# Atmega328P_Shield.net
KiCad netlist of a schematic drawn in Altium Designer
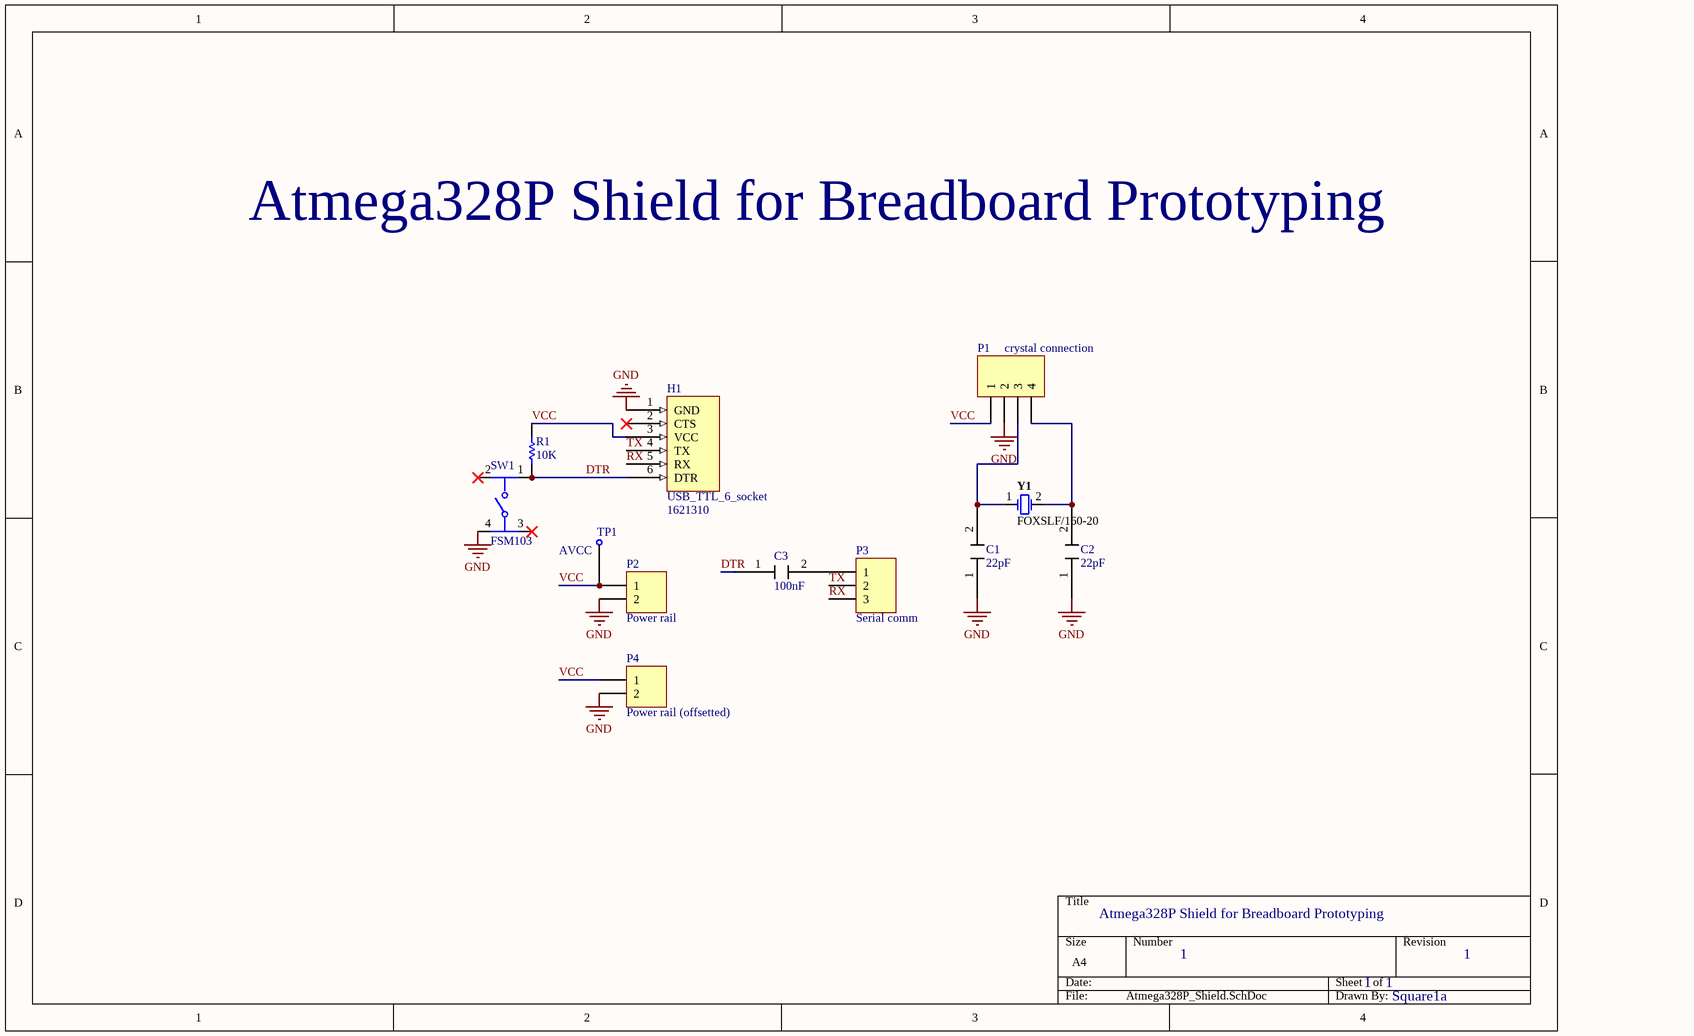
[diagram p0: Atmega328P_Shield.SchDoc]

(export (version "E")
  (design (tool "Eeschema 10.0.6"))
  (components
    (comp (ref "C1")
      (value "22pF")
      (footprint "Ceramic Capacitor")
      (libsource (lib "shared_schemLib") (part "capacitor"))
    )
    (comp (ref "C2")
      (value "22pF")
      (footprint "Ceramic Capacitor")
      (libsource (lib "shared_schemLib") (part "capacitor"))
    )
    (comp (ref "C3")
      (value "100nF")
      (footprint "Ceramic Capacitor")
      (libsource (lib "shared_schemLib") (part "capacitor"))
    )
    (comp (ref "H1")
      (value "USB_TTL_6_socket")
      (footprint "TTL USB (6 SOCKETS)")
      (fields (field (name "SUPPLIER PART NUMBER 1") "1621310"))
      (libsource (lib "shared_schemLib") (part "USB_TTL_6_socket"))
    )
    (comp (ref "P1")
      (value "crystal connection")
      (footprint "HDR1X4")
      (description "Header, 4-Pin")
      (fields (field (name "PUBLISHER") "Altium Limited"))
      (libsource (lib "Miscellaneous Connectors") (part "Header 4"))
    )
    (comp (ref "P2")
      (value "Power rail")
      (footprint "HDR1X2")
      (description "Header, 2-Pin")
      (fields (field (name "PUBLISHER") "Altium Limited"))
      (libsource (lib "Miscellaneous Connectors") (part "Header 2"))
    )
    (comp (ref "P3")
      (value "Serial comm")
      (footprint "HDR1X3")
      (description "Header, 3-Pin")
      (fields (field (name "PUBLISHER") "Altium Limited"))
      (libsource (lib "Miscellaneous Connectors") (part "Header 3"))
    )
    (comp (ref "P4")
      (value "Power rail (offsetted)")
      (footprint "HDR1X2")
      (description "Header, 2-Pin")
      (fields (field (name "PUBLISHER") "Altium Limited"))
      (libsource (lib "Miscellaneous Connectors") (part "Header 2"))
    )
    (comp (ref "R1")
      (value "10K")
      (footprint "AXIAL-0.3")
      (description "Resistor")
      (fields (field (name "PUBLISHER") "Altium Limited"))
      (libsource (lib "Miscellaneous Devices") (part "Res1"))
    )
    (comp (ref "SW1")
      (value "FSM103")
      (footprint "FP-FSM103-MFG")
      (description "SWITCH TACTILE SPST-NO 0.05A 24V")
      (libsource (lib "Altium Content Vault") (part "c0df99d12937e9d2da15afdedf14b17"))
    )
    (comp (ref "TP1")
      (value "AVCC")
      (footprint "TEST_POINT")
      (description "Polyurethane Multi-Purpose Cream Adhesive, 10.3 oz Cartridge")
      (fields
        (field (name "MANUFACTURER") "Keystone Electronics")
        (field (name "MANUFACTURER PART NUMBER") "5010")
      )
      (libsource (lib "shared_schemLib") (part "Testpoint"))
    )
    (comp (ref "Y1")
      (value "FOXSLF/160-20")
      (footprint "FOX-FOXSLF160-20")
      (description "Resistance Weld Thru-Hole Crystal, 16 MHz, -20 to 70 degC, 2-Pin THD, RoHS, Bulk")
      (fields (field (name "TOLERANCE") "1%"))
      (libsource (lib "Altium Content Vault") (part "XTAL-1-2-2"))
    )
  )
  (nets
    (net (code "1") (name "/DTR") (class "Default")
      (node (ref "C3") (pin "1") (pinfunction "1_1") (pintype "passive"))
      (node (ref "H1") (pin "6") (pinfunction "DTR_6") (pintype "input"))
      (node (ref "R1") (pin "2") (pinfunction "2_2") (pintype "passive"))
      (node (ref "SW1") (pin "1") (pinfunction "1_1") (pintype "passive"))
    )
    (net (code "2") (name "/RX") (class "Default")
      (node (ref "H1") (pin "5") (pinfunction "RX_5") (pintype "input"))
      (node (ref "P3") (pin "3") (pinfunction "3_3") (pintype "passive"))
    )
    (net (code "3") (name "/TX") (class "Default")
      (node (ref "H1") (pin "4") (pinfunction "TX_4") (pintype "input"))
      (node (ref "P3") (pin "2") (pinfunction "2_2") (pintype "passive"))
    )
    (net (code "4") (name "/VCC") (class "Default")
      (node (ref "H1") (pin "3") (pinfunction "VCC_3") (pintype "input"))
      (node (ref "P1") (pin "1") (pinfunction "1_1") (pintype "passive"))
      (node (ref "P2") (pin "1") (pinfunction "1_1") (pintype "passive"))
      (node (ref "P4") (pin "1") (pinfunction "1_1") (pintype "passive"))
      (node (ref "R1") (pin "1") (pinfunction "1_1") (pintype "passive"))
      (node (ref "TP1") (pin "1") (pinfunction "1_1") (pintype "passive"))
    )
    (net (code "5") (name "GND") (class "Default")
      (node (ref "C1") (pin "1") (pinfunction "1_1") (pintype "passive"))
      (node (ref "C2") (pin "1") (pinfunction "1_1") (pintype "passive"))
      (node (ref "H1") (pin "1") (pinfunction "GND_1") (pintype "input"))
      (node (ref "P1") (pin "2") (pinfunction "2_2") (pintype "passive"))
      (node (ref "P2") (pin "2") (pinfunction "2_2") (pintype "passive"))
      (node (ref "P4") (pin "2") (pinfunction "2_2") (pintype "passive"))
      (node (ref "SW1") (pin "4") (pinfunction "4_4") (pintype "passive"))
    )
    (net (code "6") (name "Net-(C1-Pad2)") (class "Default")
      (node (ref "C1") (pin "2") (pinfunction "2_2") (pintype "passive"))
      (node (ref "P1") (pin "3") (pinfunction "3_3") (pintype "passive"))
      (node (ref "Y1") (pin "1") (pinfunction "1_1") (pintype "passive"))
    )
    (net (code "7") (name "Net-(C2-Pad2)") (class "Default")
      (node (ref "C2") (pin "2") (pinfunction "2_2") (pintype "passive"))
      (node (ref "P1") (pin "4") (pinfunction "4_4") (pintype "passive"))
      (node (ref "Y1") (pin "2") (pinfunction "2_2") (pintype "passive"))
    )
    (net (code "8") (name "Net-(C3-Pad2)") (class "Default")
      (node (ref "C3") (pin "2") (pinfunction "2_2") (pintype "passive"))
      (node (ref "P3") (pin "1") (pinfunction "1_1") (pintype "passive"))
    )
    (net (code "9") (name "unconnected-(H1-CTS-Pad2)") (class "Default")
      (node (ref "H1") (pin "2") (pinfunction "CTS_2") (pintype "input+no_connect"))
    )
    (net (code "10") (name "unconnected-(SW1-Pad2)") (class "Default")
      (node (ref "SW1") (pin "2") (pinfunction "2_2") (pintype "passive+no_connect"))
    )
    (net (code "11") (name "unconnected-(SW1-Pad3)") (class "Default")
      (node (ref "SW1") (pin "3") (pinfunction "3_3") (pintype "passive+no_connect"))
    )
  )
)
